# display.net
KiCad netlist of a schematic drawn in EAGLE
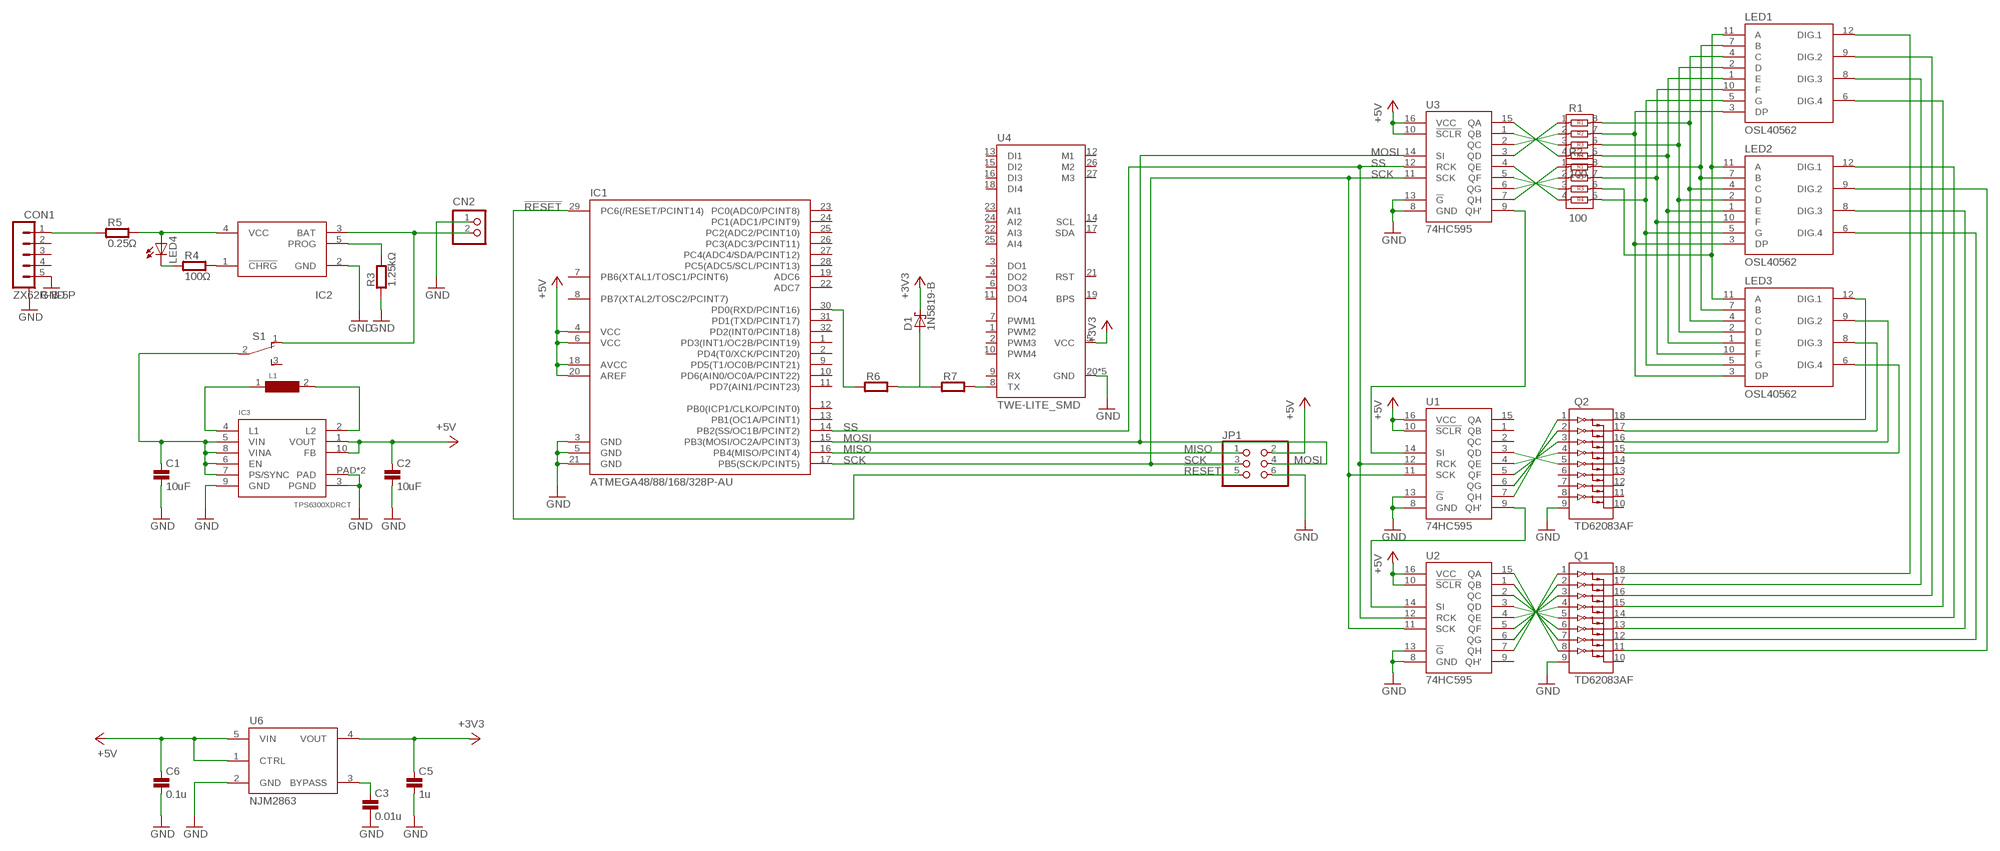
[diagram p0: schematic, sheet 1]

(export (version "E")
  (design (tool "Eeschema 10.0.6"))
  (components
    (comp (ref "C1")
      (value "10uF")
      (footprint "eagle-import:0603@1")
      (libsource (lib "eagle-import") (part "C0603"))
    )
    (comp (ref "C2")
      (value "10uF")
      (footprint "eagle-import:0603@1")
      (libsource (lib "eagle-import") (part "C0603"))
    )
    (comp (ref "C3")
      (value "0.01u")
      (footprint "eagle-import:0603@1")
      (libsource (lib "eagle-import") (part "C0603"))
    )
    (comp (ref "C5")
      (value "1u")
      (footprint "eagle-import:0603@1")
      (libsource (lib "eagle-import") (part "C0603"))
    )
    (comp (ref "C6")
      (value "0.1u")
      (footprint "eagle-import:0603@1")
      (libsource (lib "eagle-import") (part "C0603"))
    )
    (comp (ref "CN2")
      (value "S2B-PH-K-S")
      (footprint "eagle-import:S2B-PH-K-S")
      (libsource (lib "eagle-import") (part "S2B-PH-K-S"))
    )
    (comp (ref "CON1")
      (value "ZX62R-B-5P")
      (footprint "eagle-import:MICRO-B")
      (libsource (lib "eagle-import") (part "ZX62R-B-5P"))
    )
    (comp (ref "D1")
      (value "1N5819-B")
      (footprint "eagle-import:DO41-7.6")
      (libsource (lib "eagle-import") (part "1N5819-B"))
    )
    (comp (ref "IC1")
      (value "ATMEGA48/88/168/328P-AU")
      (footprint "eagle-import:TQFP32")
      (libsource (lib "eagle-import") (part "ATMEGA48/88/168/328P-AU"))
    )
    (comp (ref "IC2")
      (value "LTC4054")
      (footprint "eagle-import:TSOT23-5")
      (libsource (lib "eagle-import") (part "LTC4054"))
    )
    (comp (ref "IC3")
      (value "TPS6300XDRCT")
      (footprint "eagle-import:S-PVSON-N10")
      (libsource (lib "eagle-import") (part "TPS6300XDRCT"))
    )
    (comp (ref "JP1")
      (value "PINHD-2X3")
      (footprint "eagle-import:2X03")
      (libsource (lib "eagle-import") (part "PINHD-2X3"))
    )
    (comp (ref "L1")
      (value "VLF4012ST")
      (footprint "eagle-import:VLF4012ST")
      (libsource (lib "eagle-import") (part "VLF4012ST"))
    )
    (comp (ref "LED1")
      (value "OSL40562")
      (footprint "eagle-import:7SEG_4DIG")
      (libsource (lib "eagle-import") (part "OSL40562"))
    )
    (comp (ref "LED2")
      (value "OSL40562")
      (footprint "eagle-import:7SEG_4DIG")
      (libsource (lib "eagle-import") (part "OSL40562"))
    )
    (comp (ref "LED3")
      (value "OSL40562")
      (footprint "eagle-import:7SEG_4DIG")
      (libsource (lib "eagle-import") (part "OSL40562"))
    )
    (comp (ref "LED4")
      (value "LEDSML0603")
      (footprint "eagle-import:SML0603")
      (libsource (lib "eagle-import") (part "LEDSML0603"))
    )
    (comp (ref "Q1")
      (value "TD62083AF")
      (footprint "eagle-import:SOP18")
      (libsource (lib "eagle-import") (part "TD62083AF"))
    )
    (comp (ref "Q2")
      (value "TD62083AF")
      (footprint "eagle-import:SOP18")
      (libsource (lib "eagle-import") (part "TD62083AF"))
    )
    (comp (ref "R1")
      (value "100")
      (footprint "eagle-import:BCN164AB")
      (libsource (lib "eagle-import") (part "BCN164AB"))
    )
    (comp (ref "R2")
      (value "100")
      (footprint "eagle-import:BCN164AB")
      (libsource (lib "eagle-import") (part "BCN164AB"))
    )
    (comp (ref "R3")
      (value "1.25kΩ")
      (footprint "eagle-import:0603")
      (libsource (lib "eagle-import") (part "R0603"))
    )
    (comp (ref "R4")
      (value "100Ω")
      (footprint "eagle-import:0603")
      (libsource (lib "eagle-import") (part "R0603"))
    )
    (comp (ref "R5")
      (value "0.25Ω")
      (footprint "eagle-import:0603")
      (libsource (lib "eagle-import") (part "R0603"))
    )
    (comp (ref "R6")
      (value "R0204/5")
      (footprint "eagle-import:0204_5")
      (libsource (lib "eagle-import") (part "R0204/5"))
    )
    (comp (ref "R7")
      (value "R0204/5")
      (footprint "eagle-import:0204_5")
      (libsource (lib "eagle-import") (part "R0204/5"))
    )
    (comp (ref "S1")
      (value "SS-12D00")
      (footprint "eagle-import:SS-12D00")
      (libsource (lib "eagle-import") (part "SS-12D00"))
    )
    (comp (ref "U1")
      (value "74HC595")
      (footprint "eagle-import:SOP16")
      (libsource (lib "eagle-import") (part "74HC595"))
    )
    (comp (ref "U2")
      (value "74HC595")
      (footprint "eagle-import:SOP16")
      (libsource (lib "eagle-import") (part "74HC595"))
    )
    (comp (ref "U3")
      (value "74HC595")
      (footprint "eagle-import:SOP16")
      (libsource (lib "eagle-import") (part "74HC595"))
    )
    (comp (ref "U4")
      (value "TWE-LITE_SMD")
      (footprint "eagle-import:LITE")
      (libsource (lib "eagle-import") (part "TWE-LITE_SMD"))
    )
    (comp (ref "U6")
      (value "NJM2863")
      (footprint "eagle-import:SOT23_5PIN")
      (libsource (lib "eagle-import") (part "NJM2863"))
    )
  )
  (nets
    (net (code "1") (name "+3V3") (class "Default")
      (node (ref "C5") (pin "1") (pinfunction "P$1_1") (pintype "passive"))
      (node (ref "D1") (pin "C") (pinfunction "C_C") (pintype "passive"))
      (node (ref "U4") (pin "5") (pinfunction "VCC_5") (pintype "power_in"))
      (node (ref "U6") (pin "4") (pinfunction "VOUT_4") (pintype "output"))
    )
    (net (code "2") (name "+5V") (class "Default")
      (node (ref "C2") (pin "1") (pinfunction "P$1_1") (pintype "passive"))
      (node (ref "C6") (pin "1") (pinfunction "P$1_1") (pintype "passive"))
      (node (ref "IC1") (pin "18") (pinfunction "AVCC_18") (pintype "passive"))
      (node (ref "IC1") (pin "20") (pinfunction "AREF_20") (pintype "passive"))
      (node (ref "IC1") (pin "4") (pinfunction "VCC_4") (pintype "power_in"))
      (node (ref "IC1") (pin "6") (pinfunction "VCC_6") (pintype "power_in"))
      (node (ref "IC3") (pin "1") (pinfunction "VOUT_1") (pintype "output"))
      (node (ref "IC3") (pin "10") (pinfunction "FB_10") (pintype "input"))
      (node (ref "JP1") (pin "2") (pinfunction "2_2") (pintype "passive"))
      (node (ref "U1") (pin "10") (pinfunction "~{SCLR}_10") (pintype "input"))
      (node (ref "U1") (pin "16") (pinfunction "VCC_16") (pintype "power_in"))
      (node (ref "U2") (pin "10") (pinfunction "~{SCLR}_10") (pintype "input"))
      (node (ref "U2") (pin "16") (pinfunction "VCC_16") (pintype "power_in"))
      (node (ref "U3") (pin "10") (pinfunction "~{SCLR}_10") (pintype "input"))
      (node (ref "U3") (pin "16") (pinfunction "VCC_16") (pintype "power_in"))
      (node (ref "U6") (pin "1") (pinfunction "CTRL_1") (pintype "input"))
      (node (ref "U6") (pin "5") (pinfunction "VIN_5") (pintype "input"))
    )
    (net (code "3") (name "/MISO") (class "Default")
      (node (ref "IC1") (pin "16") (pinfunction "PB4(MISO/PCINT4)_16") (pintype "bidirectional"))
      (node (ref "JP1") (pin "1") (pinfunction "1_1") (pintype "passive"))
    )
    (net (code "4") (name "/MOSI") (class "Default")
      (node (ref "IC1") (pin "15") (pinfunction "PB3(MOSI/OC2A/PCINT3)_15") (pintype "bidirectional"))
      (node (ref "JP1") (pin "4") (pinfunction "4_4") (pintype "passive"))
      (node (ref "U3") (pin "14") (pinfunction "SI_14") (pintype "input"))
    )
    (net (code "5") (name "/SCK") (class "Default")
      (node (ref "IC1") (pin "17") (pinfunction "PB5(SCK/PCINT5)_17") (pintype "bidirectional"))
      (node (ref "JP1") (pin "3") (pinfunction "3_3") (pintype "passive"))
      (node (ref "U1") (pin "11") (pinfunction "SCK_11") (pintype "input"))
      (node (ref "U2") (pin "11") (pinfunction "SCK_11") (pintype "input"))
      (node (ref "U3") (pin "11") (pinfunction "SCK_11") (pintype "input"))
    )
    (net (code "6") (name "/SS") (class "Default")
      (node (ref "IC1") (pin "14") (pinfunction "PB2(SS/OC1B/PCINT2)_14") (pintype "bidirectional"))
      (node (ref "U1") (pin "12") (pinfunction "RCK_12") (pintype "input"))
      (node (ref "U2") (pin "12") (pinfunction "RCK_12") (pintype "input"))
      (node (ref "U3") (pin "12") (pinfunction "RCK_12") (pintype "input"))
    )
    (net (code "7") (name "/~{RESET}") (class "Default")
      (node (ref "IC1") (pin "29") (pinfunction "PC6(/RESET/PCINT14)_29") (pintype "bidirectional"))
      (node (ref "JP1") (pin "5") (pinfunction "5_5") (pintype "passive"))
    )
    (net (code "8") (name "GND") (class "Default")
      (node (ref "C1") (pin "2") (pinfunction "P$2_2") (pintype "passive"))
      (node (ref "C2") (pin "2") (pinfunction "P$2_2") (pintype "passive"))
      (node (ref "C3") (pin "2") (pinfunction "P$2_2") (pintype "passive"))
      (node (ref "C5") (pin "2") (pinfunction "P$2_2") (pintype "passive"))
      (node (ref "C6") (pin "2") (pinfunction "P$2_2") (pintype "passive"))
      (node (ref "CN2") (pin "1") (pinfunction "1_1") (pintype "passive"))
      (node (ref "CON1") (pin "5") (pinfunction "5.GND_5") (pintype "passive"))
      (node (ref "CON1") (pin "CASE@1") (pinfunction "P$1_CASE@1") (pintype "bidirectional"))
      (node (ref "CON1") (pin "CASE@2") (pinfunction "P$1_CASE@2") (pintype "bidirectional"))
      (node (ref "CON1") (pin "CASE@3") (pinfunction "P$1_CASE@3") (pintype "bidirectional"))
      (node (ref "CON1") (pin "CASE@4") (pinfunction "P$1_CASE@4") (pintype "bidirectional"))
      (node (ref "IC1") (pin "21") (pinfunction "GND_21") (pintype "power_in"))
      (node (ref "IC1") (pin "3") (pinfunction "GND_3") (pintype "power_in"))
      (node (ref "IC1") (pin "5") (pinfunction "GND_5") (pintype "power_in"))
      (node (ref "IC2") (pin "2") (pinfunction "GND_2") (pintype "power_in"))
      (node (ref "IC3") (pin "3") (pinfunction "PGND_3") (pintype "power_in"))
      (node (ref "IC3") (pin "9") (pinfunction "GND_9") (pintype "power_in"))
      (node (ref "IC3") (pin "PAD") (pinfunction "PAD_PAD") (pintype "power_in"))
      (node (ref "IC3") (pin "PAD@1") (pinfunction "PAD_PAD@1") (pintype "power_in"))
      (node (ref "JP1") (pin "6") (pinfunction "6_6") (pintype "passive"))
      (node (ref "Q1") (pin "9") (pinfunction "GND_9") (pintype "power_in"))
      (node (ref "Q2") (pin "9") (pinfunction "GND_9") (pintype "power_in"))
      (node (ref "R3") (pin "1") (pinfunction "P$1_1") (pintype "passive"))
      (node (ref "U1") (pin "13") (pinfunction "~{G}_13") (pintype "input"))
      (node (ref "U1") (pin "8") (pinfunction "GND_8") (pintype "power_in"))
      (node (ref "U2") (pin "13") (pinfunction "~{G}_13") (pintype "input"))
      (node (ref "U2") (pin "8") (pinfunction "GND_8") (pintype "power_in"))
      (node (ref "U3") (pin "13") (pinfunction "~{G}_13") (pintype "input"))
      (node (ref "U3") (pin "8") (pinfunction "GND_8") (pintype "power_in"))
      (node (ref "U4") (pin "20") (pinfunction "GND_20") (pintype "power_in"))
      (node (ref "U4") (pin "28") (pinfunction "GND_28") (pintype "power_in"))
      (node (ref "U4") (pin "30") (pinfunction "GND_30") (pintype "power_in"))
      (node (ref "U4") (pin "31") (pinfunction "GND_31") (pintype "power_in"))
      (node (ref "U4") (pin "32") (pinfunction "GND_32") (pintype "power_in"))
      (node (ref "U6") (pin "2") (pinfunction "GND_2") (pintype "power_in"))
    )
    (net (code "9") (name "Net-(C1-P$1)") (class "Default")
      (node (ref "C1") (pin "1") (pinfunction "P$1_1") (pintype "passive"))
      (node (ref "IC3") (pin "5") (pinfunction "VIN_5") (pintype "power_in"))
      (node (ref "IC3") (pin "6") (pinfunction "EN_6") (pintype "input"))
      (node (ref "IC3") (pin "7") (pinfunction "PS/SYNC_7") (pintype "input"))
      (node (ref "IC3") (pin "8") (pinfunction "VINA_8") (pintype "power_in"))
      (node (ref "S1") (pin "2") (pinfunction "P_2") (pintype "passive"))
    )
    (net (code "10") (name "Net-(C3-P$1)") (class "Default")
      (node (ref "C3") (pin "1") (pinfunction "P$1_1") (pintype "passive"))
      (node (ref "U6") (pin "3") (pinfunction "BYPASS_3") (pintype "passive"))
    )
    (net (code "11") (name "Net-(CON1-1.VBUS)") (class "Default")
      (node (ref "CON1") (pin "1") (pinfunction "1.VBUS_1") (pintype "passive"))
      (node (ref "R5") (pin "1") (pinfunction "P$1_1") (pintype "passive"))
    )
    (net (code "12") (name "Net-(IC1-PD0(RXD{slash}PCINT16))") (class "Default")
      (node (ref "IC1") (pin "30") (pinfunction "PD0(RXD/PCINT16)_30") (pintype "bidirectional"))
      (node (ref "R6") (pin "1") (pinfunction "P$1_1") (pintype "passive"))
    )
    (net (code "13") (name "Net-(IC2-BAT)") (class "Default")
      (node (ref "CN2") (pin "2") (pinfunction "2_2") (pintype "passive"))
      (node (ref "IC2") (pin "3") (pinfunction "BAT_3") (pintype "power_in"))
      (node (ref "S1") (pin "1") (pinfunction "O_1") (pintype "passive"))
    )
    (net (code "14") (name "Net-(IC2-PROG)") (class "Default")
      (node (ref "IC2") (pin "5") (pinfunction "PROG_5") (pintype "passive"))
      (node (ref "R3") (pin "2") (pinfunction "P$2_2") (pintype "passive"))
    )
    (net (code "15") (name "Net-(IC2-VCC)") (class "Default")
      (node (ref "IC2") (pin "4") (pinfunction "VCC_4") (pintype "power_in"))
      (node (ref "LED4") (pin "A") (pinfunction "A_A") (pintype "passive"))
      (node (ref "R5") (pin "2") (pinfunction "P$2_2") (pintype "passive"))
    )
    (net (code "16") (name "Net-(IC2-~{CHRG})") (class "Default")
      (node (ref "IC2") (pin "1") (pinfunction "~{CHRG}_1") (pintype "output"))
      (node (ref "R4") (pin "2") (pinfunction "P$2_2") (pintype "passive"))
    )
    (net (code "17") (name "Net-(IC3-L1)") (class "Default")
      (node (ref "IC3") (pin "4") (pinfunction "L1_4") (pintype "bidirectional"))
      (node (ref "L1") (pin "1") (pinfunction "1_1") (pintype "passive"))
    )
    (net (code "18") (name "Net-(IC3-L2)") (class "Default")
      (node (ref "IC3") (pin "2") (pinfunction "L2_2") (pintype "bidirectional"))
      (node (ref "L1") (pin "2") (pinfunction "2_2") (pintype "passive"))
    )
    (net (code "19") (name "Net-(LED1-A)") (class "Default")
      (node (ref "LED1") (pin "11") (pinfunction "A_11") (pintype "input"))
      (node (ref "LED2") (pin "11") (pinfunction "A_11") (pintype "input"))
      (node (ref "LED3") (pin "11") (pinfunction "A_11") (pintype "input"))
      (node (ref "R2") (pin "6") (pinfunction "6_6") (pintype "passive"))
    )
    (net (code "20") (name "Net-(LED1-B)") (class "Default")
      (node (ref "LED1") (pin "7") (pinfunction "B_7") (pintype "input"))
      (node (ref "LED2") (pin "7") (pinfunction "B_7") (pintype "input"))
      (node (ref "LED3") (pin "7") (pinfunction "B_7") (pintype "input"))
      (node (ref "R2") (pin "8") (pinfunction "8_8") (pintype "passive"))
    )
    (net (code "21") (name "Net-(LED1-C)") (class "Default")
      (node (ref "LED1") (pin "4") (pinfunction "C_4") (pintype "input"))
      (node (ref "LED2") (pin "4") (pinfunction "C_4") (pintype "input"))
      (node (ref "LED3") (pin "4") (pinfunction "C_4") (pintype "input"))
      (node (ref "R1") (pin "8") (pinfunction "8_8") (pintype "passive"))
    )
    (net (code "22") (name "Net-(LED1-D)") (class "Default")
      (node (ref "LED1") (pin "2") (pinfunction "D_2") (pintype "input"))
      (node (ref "LED2") (pin "2") (pinfunction "D_2") (pintype "input"))
      (node (ref "LED3") (pin "2") (pinfunction "D_2") (pintype "input"))
      (node (ref "R1") (pin "6") (pinfunction "6_6") (pintype "passive"))
    )
    (net (code "23") (name "Net-(LED1-DIG.1)") (class "Default")
      (node (ref "LED1") (pin "12") (pinfunction "DIG.1_12") (pintype "output"))
      (node (ref "Q1") (pin "18") (pinfunction "O1_18") (pintype "output"))
    )
    (net (code "24") (name "Net-(LED1-DIG.2)") (class "Default")
      (node (ref "LED1") (pin "9") (pinfunction "DIG.2_9") (pintype "output"))
      (node (ref "Q1") (pin "16") (pinfunction "O3_16") (pintype "output"))
    )
    (net (code "25") (name "Net-(LED1-DIG.3)") (class "Default")
      (node (ref "LED1") (pin "8") (pinfunction "DIG.3_8") (pintype "output"))
      (node (ref "Q1") (pin "17") (pinfunction "O2_17") (pintype "output"))
    )
    (net (code "26") (name "Net-(LED1-DIG.4)") (class "Default")
      (node (ref "LED1") (pin "6") (pinfunction "DIG.4_6") (pintype "output"))
      (node (ref "Q1") (pin "15") (pinfunction "O4_15") (pintype "output"))
    )
    (net (code "27") (name "Net-(LED1-DP)") (class "Default")
      (node (ref "LED1") (pin "3") (pinfunction "DP_3") (pintype "input"))
      (node (ref "LED2") (pin "3") (pinfunction "DP_3") (pintype "input"))
      (node (ref "LED3") (pin "3") (pinfunction "DP_3") (pintype "input"))
      (node (ref "R1") (pin "7") (pinfunction "7_7") (pintype "passive"))
    )
    (net (code "28") (name "Net-(LED1-E)") (class "Default")
      (node (ref "LED1") (pin "1") (pinfunction "E_1") (pintype "input"))
      (node (ref "LED2") (pin "1") (pinfunction "E_1") (pintype "input"))
      (node (ref "LED3") (pin "1") (pinfunction "E_1") (pintype "input"))
      (node (ref "R1") (pin "5") (pinfunction "5_5") (pintype "passive"))
    )
    (net (code "29") (name "Net-(LED1-F)") (class "Default")
      (node (ref "LED1") (pin "10") (pinfunction "F_10") (pintype "input"))
      (node (ref "LED2") (pin "10") (pinfunction "F_10") (pintype "input"))
      (node (ref "LED3") (pin "10") (pinfunction "F_10") (pintype "input"))
      (node (ref "R2") (pin "7") (pinfunction "7_7") (pintype "passive"))
    )
    (net (code "30") (name "Net-(LED1-G)") (class "Default")
      (node (ref "LED1") (pin "5") (pinfunction "G_5") (pintype "input"))
      (node (ref "LED2") (pin "5") (pinfunction "G_5") (pintype "input"))
      (node (ref "LED3") (pin "5") (pinfunction "G_5") (pintype "input"))
      (node (ref "R2") (pin "5") (pinfunction "5_5") (pintype "passive"))
    )
    (net (code "31") (name "Net-(LED2-DIG.1)") (class "Default")
      (node (ref "LED2") (pin "12") (pinfunction "DIG.1_12") (pintype "output"))
      (node (ref "Q1") (pin "14") (pinfunction "O5_14") (pintype "output"))
    )
    (net (code "32") (name "Net-(LED2-DIG.2)") (class "Default")
      (node (ref "LED2") (pin "9") (pinfunction "DIG.2_9") (pintype "output"))
      (node (ref "Q1") (pin "11") (pinfunction "O8_11") (pintype "output"))
    )
    (net (code "33") (name "Net-(LED2-DIG.3)") (class "Default")
      (node (ref "LED2") (pin "8") (pinfunction "DIG.3_8") (pintype "output"))
      (node (ref "Q1") (pin "13") (pinfunction "O6_13") (pintype "output"))
    )
    (net (code "34") (name "Net-(LED2-DIG.4)") (class "Default")
      (node (ref "LED2") (pin "6") (pinfunction "DIG.4_6") (pintype "output"))
      (node (ref "Q1") (pin "12") (pinfunction "O7_12") (pintype "output"))
    )
    (net (code "35") (name "Net-(LED3-DIG.1)") (class "Default")
      (node (ref "LED3") (pin "12") (pinfunction "DIG.1_12") (pintype "output"))
      (node (ref "Q2") (pin "18") (pinfunction "O1_18") (pintype "output"))
    )
    (net (code "36") (name "Net-(LED3-DIG.2)") (class "Default")
      (node (ref "LED3") (pin "9") (pinfunction "DIG.2_9") (pintype "output"))
      (node (ref "Q2") (pin "16") (pinfunction "O3_16") (pintype "output"))
    )
    (net (code "37") (name "Net-(LED3-DIG.3)") (class "Default")
      (node (ref "LED3") (pin "8") (pinfunction "DIG.3_8") (pintype "output"))
      (node (ref "Q2") (pin "17") (pinfunction "O2_17") (pintype "output"))
    )
    (net (code "38") (name "Net-(LED3-DIG.4)") (class "Default")
      (node (ref "LED3") (pin "6") (pinfunction "DIG.4_6") (pintype "output"))
      (node (ref "Q2") (pin "15") (pinfunction "O4_15") (pintype "output"))
    )
    (net (code "39") (name "Net-(Q1-I1)") (class "Default")
      (node (ref "Q1") (pin "1") (pinfunction "I1_1") (pintype "input"))
      (node (ref "U2") (pin "7") (pinfunction "QH_7") (pintype "output"))
    )
    (net (code "40") (name "Net-(Q1-I2)") (class "Default")
      (node (ref "Q1") (pin "2") (pinfunction "I2_2") (pintype "input"))
      (node (ref "U2") (pin "6") (pinfunction "QG_6") (pintype "output"))
    )
    (net (code "41") (name "Net-(Q1-I3)") (class "Default")
      (node (ref "Q1") (pin "3") (pinfunction "I3_3") (pintype "input"))
      (node (ref "U2") (pin "5") (pinfunction "QF_5") (pintype "output"))
    )
    (net (code "42") (name "Net-(Q1-I4)") (class "Default")
      (node (ref "Q1") (pin "4") (pinfunction "I4_4") (pintype "input"))
      (node (ref "U2") (pin "4") (pinfunction "QE_4") (pintype "output"))
    )
    (net (code "43") (name "Net-(Q1-I5)") (class "Default")
      (node (ref "Q1") (pin "5") (pinfunction "I5_5") (pintype "input"))
      (node (ref "U2") (pin "3") (pinfunction "QD_3") (pintype "output"))
    )
    (net (code "44") (name "Net-(Q1-I6)") (class "Default")
      (node (ref "Q1") (pin "6") (pinfunction "I6_6") (pintype "input"))
      (node (ref "U2") (pin "2") (pinfunction "QC_2") (pintype "output"))
    )
    (net (code "45") (name "Net-(Q1-I7)") (class "Default")
      (node (ref "Q1") (pin "7") (pinfunction "I7_7") (pintype "input"))
      (node (ref "U2") (pin "1") (pinfunction "QB_1") (pintype "output"))
    )
    (net (code "46") (name "Net-(Q1-I8)") (class "Default")
      (node (ref "Q1") (pin "8") (pinfunction "I8_8") (pintype "input"))
      (node (ref "U2") (pin "15") (pinfunction "QA_15") (pintype "output"))
    )
    (net (code "47") (name "Net-(Q2-I1)") (class "Default")
      (node (ref "Q2") (pin "1") (pinfunction "I1_1") (pintype "input"))
      (node (ref "U1") (pin "7") (pinfunction "QH_7") (pintype "output"))
    )
    (net (code "48") (name "Net-(Q2-I2)") (class "Default")
      (node (ref "Q2") (pin "2") (pinfunction "I2_2") (pintype "input"))
      (node (ref "U1") (pin "6") (pinfunction "QG_6") (pintype "output"))
    )
    (net (code "49") (name "Net-(Q2-I3)") (class "Default")
      (node (ref "Q2") (pin "3") (pinfunction "I3_3") (pintype "input"))
      (node (ref "U1") (pin "5") (pinfunction "QF_5") (pintype "output"))
    )
    (net (code "50") (name "Net-(Q2-I4)") (class "Default")
      (node (ref "Q2") (pin "4") (pinfunction "I4_4") (pintype "input"))
      (node (ref "U1") (pin "4") (pinfunction "QE_4") (pintype "output"))
    )
    (net (code "51") (name "Net-(Q2-I5)") (class "Default")
      (node (ref "Q2") (pin "5") (pinfunction "I5_5") (pintype "input"))
      (node (ref "U1") (pin "3") (pinfunction "QD_3") (pintype "output"))
    )
    (net (code "52") (name "Net-(R4-P$1)") (class "Default")
      (node (ref "LED4") (pin "C") (pinfunction "C_C") (pintype "passive"))
      (node (ref "R4") (pin "1") (pinfunction "P$1_1") (pintype "passive"))
    )
    (net (code "53") (name "Net-(R6-P$2)") (class "Default")
      (node (ref "D1") (pin "A") (pinfunction "A_A") (pintype "passive"))
      (node (ref "R6") (pin "2") (pinfunction "P$2_2") (pintype "passive"))
      (node (ref "R7") (pin "1") (pinfunction "P$1_1") (pintype "passive"))
    )
    (net (code "54") (name "Net-(R7-P$2)") (class "Default")
      (node (ref "R7") (pin "2") (pinfunction "P$2_2") (pintype "passive"))
      (node (ref "U4") (pin "8") (pinfunction "TX_8") (pintype "output"))
    )
    (net (code "55") (name "Net-(U1-QH')") (class "Default")
      (node (ref "U1") (pin "9") (pinfunction "QH'_9") (pintype "output"))
      (node (ref "U2") (pin "14") (pinfunction "SI_14") (pintype "input"))
    )
    (net (code "56") (name "Net-(U1-SI)") (class "Default")
      (node (ref "U1") (pin "14") (pinfunction "SI_14") (pintype "input"))
      (node (ref "U3") (pin "9") (pinfunction "QH'_9") (pintype "output"))
    )
    (net (code "57") (name "Net-(U3-QA)") (class "Default")
      (node (ref "R1") (pin "4") (pinfunction "4_4") (pintype "passive"))
      (node (ref "U3") (pin "15") (pinfunction "QA_15") (pintype "output"))
    )
    (net (code "58") (name "Net-(U3-QB)") (class "Default")
      (node (ref "R1") (pin "3") (pinfunction "3_3") (pintype "passive"))
      (node (ref "U3") (pin "1") (pinfunction "QB_1") (pintype "output"))
    )
    (net (code "59") (name "Net-(U3-QC)") (class "Default")
      (node (ref "R1") (pin "2") (pinfunction "2_2") (pintype "passive"))
      (node (ref "U3") (pin "2") (pinfunction "QC_2") (pintype "output"))
    )
    (net (code "60") (name "Net-(U3-QD)") (class "Default")
      (node (ref "R1") (pin "1") (pinfunction "1_1") (pintype "passive"))
      (node (ref "U3") (pin "3") (pinfunction "QD_3") (pintype "output"))
    )
    (net (code "61") (name "Net-(U3-QE)") (class "Default")
      (node (ref "R2") (pin "4") (pinfunction "4_4") (pintype "passive"))
      (node (ref "U3") (pin "4") (pinfunction "QE_4") (pintype "output"))
    )
    (net (code "62") (name "Net-(U3-QF)") (class "Default")
      (node (ref "R2") (pin "3") (pinfunction "3_3") (pintype "passive"))
      (node (ref "U3") (pin "5") (pinfunction "QF_5") (pintype "output"))
    )
    (net (code "63") (name "Net-(U3-QG)") (class "Default")
      (node (ref "R2") (pin "2") (pinfunction "2_2") (pintype "passive"))
      (node (ref "U3") (pin "6") (pinfunction "QG_6") (pintype "output"))
    )
    (net (code "64") (name "Net-(U3-QH)") (class "Default")
      (node (ref "R2") (pin "1") (pinfunction "1_1") (pintype "passive"))
      (node (ref "U3") (pin "7") (pinfunction "QH_7") (pintype "output"))
    )
    (net (code "65") (name "unconnected-(CON1-2.D--Pad2)") (class "Default")
      (node (ref "CON1") (pin "2") (pinfunction "2.D-_2") (pintype "passive"))
    )
    (net (code "66") (name "unconnected-(CON1-3.D+-Pad3)") (class "Default")
      (node (ref "CON1") (pin "3") (pinfunction "3.D+_3") (pintype "passive"))
    )
    (net (code "67") (name "unconnected-(CON1-4.ID-Pad4)") (class "Default")
      (node (ref "CON1") (pin "4") (pinfunction "4.ID_4") (pintype "passive"))
    )
    (net (code "68") (name "unconnected-(IC1-ADC6-Pad19)") (class "Default")
      (node (ref "IC1") (pin "19") (pinfunction "ADC6_19") (pintype "passive"))
    )
    (net (code "69") (name "unconnected-(IC1-ADC7-Pad22)") (class "Default")
      (node (ref "IC1") (pin "22") (pinfunction "ADC7_22") (pintype "passive"))
    )
    (net (code "70") (name "unconnected-(IC1-PB0(ICP1{slash}CLKO{slash}PCINT0)-Pad12)") (class "Default")
      (node (ref "IC1") (pin "12") (pinfunction "PB0(ICP1/CLKO/PCINT0)_12") (pintype "bidirectional"))
    )
    (net (code "71") (name "unconnected-(IC1-PB1(OC1A{slash}PCINT1)-Pad13)") (class "Default")
      (node (ref "IC1") (pin "13") (pinfunction "PB1(OC1A/PCINT1)_13") (pintype "bidirectional"))
    )
    (net (code "72") (name "unconnected-(IC1-PB6(XTAL1{slash}TOSC1{slash}PCINT6)-Pad7)") (class "Default")
      (node (ref "IC1") (pin "7") (pinfunction "PB6(XTAL1/TOSC1/PCINT6)_7") (pintype "bidirectional"))
    )
    (net (code "73") (name "unconnected-(IC1-PB7(XTAL2{slash}TOSC2{slash}PCINT7)-Pad8)") (class "Default")
      (node (ref "IC1") (pin "8") (pinfunction "PB7(XTAL2/TOSC2/PCINT7)_8") (pintype "bidirectional"))
    )
    (net (code "74") (name "unconnected-(IC1-PC0(ADC0{slash}PCINT8)-Pad23)") (class "Default")
      (node (ref "IC1") (pin "23") (pinfunction "PC0(ADC0/PCINT8)_23") (pintype "bidirectional"))
    )
    (net (code "75") (name "unconnected-(IC1-PC1(ADC1{slash}PCINT9)-Pad24)") (class "Default")
      (node (ref "IC1") (pin "24") (pinfunction "PC1(ADC1/PCINT9)_24") (pintype "bidirectional"))
    )
    (net (code "76") (name "unconnected-(IC1-PC2(ADC2{slash}PCINT10)-Pad25)") (class "Default")
      (node (ref "IC1") (pin "25") (pinfunction "PC2(ADC2/PCINT10)_25") (pintype "bidirectional"))
    )
    (net (code "77") (name "unconnected-(IC1-PC3(ADC3{slash}PCINT11)-Pad26)") (class "Default")
      (node (ref "IC1") (pin "26") (pinfunction "PC3(ADC3/PCINT11)_26") (pintype "bidirectional"))
    )
    (net (code "78") (name "unconnected-(IC1-PC4(ADC4{slash}SDA{slash}PCINT12)-Pad27)") (class "Default")
      (node (ref "IC1") (pin "27") (pinfunction "PC4(ADC4/SDA/PCINT12)_27") (pintype "bidirectional"))
    )
    (net (code "79") (name "unconnected-(IC1-PC5(ADC5{slash}SCL{slash}PCINT13)-Pad28)") (class "Default")
      (node (ref "IC1") (pin "28") (pinfunction "PC5(ADC5/SCL/PCINT13)_28") (pintype "bidirectional"))
    )
    (net (code "80") (name "unconnected-(IC1-PD1(TXD{slash}PCINT17)-Pad31)") (class "Default")
      (node (ref "IC1") (pin "31") (pinfunction "PD1(TXD/PCINT17)_31") (pintype "bidirectional"))
    )
    (net (code "81") (name "unconnected-(IC1-PD2(INT0{slash}PCINT18)-Pad32)") (class "Default")
      (node (ref "IC1") (pin "32") (pinfunction "PD2(INT0/PCINT18)_32") (pintype "bidirectional"))
    )
    (net (code "82") (name "unconnected-(IC1-PD3(INT1{slash}OC2B{slash}PCINT19)-Pad1)") (class "Default")
      (node (ref "IC1") (pin "1") (pinfunction "PD3(INT1/OC2B/PCINT19)_1") (pintype "bidirectional"))
    )
    (net (code "83") (name "unconnected-(IC1-PD4(T0{slash}XCK{slash}PCINT20)-Pad2)") (class "Default")
      (node (ref "IC1") (pin "2") (pinfunction "PD4(T0/XCK/PCINT20)_2") (pintype "bidirectional"))
    )
    (net (code "84") (name "unconnected-(IC1-PD5(T1{slash}OC0B{slash}PCINT21)-Pad9)") (class "Default")
      (node (ref "IC1") (pin "9") (pinfunction "PD5(T1/OC0B/PCINT21)_9") (pintype "bidirectional"))
    )
    (net (code "85") (name "unconnected-(IC1-PD6(AIN0{slash}OC0A{slash}PCINT22)-Pad10)") (class "Default")
      (node (ref "IC1") (pin "10") (pinfunction "PD6(AIN0/OC0A/PCINT22)_10") (pintype "bidirectional"))
    )
    (net (code "86") (name "unconnected-(IC1-PD7(AIN1{slash}PCINT23)-Pad11)") (class "Default")
      (node (ref "IC1") (pin "11") (pinfunction "PD7(AIN1/PCINT23)_11") (pintype "bidirectional"))
    )
    (net (code "87") (name "unconnected-(Q1-COMMON-Pad10)") (class "Default")
      (node (ref "Q1") (pin "10") (pinfunction "COMMON_10") (pintype "output"))
    )
    (net (code "88") (name "unconnected-(Q2-COMMON-Pad10)") (class "Default")
      (node (ref "Q2") (pin "10") (pinfunction "COMMON_10") (pintype "output"))
    )
    (net (code "89") (name "unconnected-(Q2-I6-Pad6)") (class "Default")
      (node (ref "Q2") (pin "6") (pinfunction "I6_6") (pintype "input"))
    )
    (net (code "90") (name "unconnected-(Q2-I7-Pad7)") (class "Default")
      (node (ref "Q2") (pin "7") (pinfunction "I7_7") (pintype "input"))
    )
    (net (code "91") (name "unconnected-(Q2-I8-Pad8)") (class "Default")
      (node (ref "Q2") (pin "8") (pinfunction "I8_8") (pintype "input"))
    )
    (net (code "92") (name "unconnected-(Q2-O5-Pad14)") (class "Default")
      (node (ref "Q2") (pin "14") (pinfunction "O5_14") (pintype "output"))
    )
    (net (code "93") (name "unconnected-(Q2-O6-Pad13)") (class "Default")
      (node (ref "Q2") (pin "13") (pinfunction "O6_13") (pintype "output"))
    )
    (net (code "94") (name "unconnected-(Q2-O7-Pad12)") (class "Default")
      (node (ref "Q2") (pin "12") (pinfunction "O7_12") (pintype "output"))
    )
    (net (code "95") (name "unconnected-(Q2-O8-Pad11)") (class "Default")
      (node (ref "Q2") (pin "11") (pinfunction "O8_11") (pintype "output"))
    )
    (net (code "96") (name "unconnected-(S1-S-Pad3)") (class "Default")
      (node (ref "S1") (pin "3") (pinfunction "S_3") (pintype "passive"))
    )
    (net (code "97") (name "unconnected-(U1-QA-Pad15)") (class "Default")
      (node (ref "U1") (pin "15") (pinfunction "QA_15") (pintype "output"))
    )
    (net (code "98") (name "unconnected-(U1-QB-Pad1)") (class "Default")
      (node (ref "U1") (pin "1") (pinfunction "QB_1") (pintype "output"))
    )
    (net (code "99") (name "unconnected-(U1-QC-Pad2)") (class "Default")
      (node (ref "U1") (pin "2") (pinfunction "QC_2") (pintype "output"))
    )
    (net (code "100") (name "unconnected-(U2-QH'-Pad9)") (class "Default")
      (node (ref "U2") (pin "9") (pinfunction "QH'_9") (pintype "output"))
    )
    (net (code "101") (name "unconnected-(U4-AI1-Pad23)") (class "Default")
      (node (ref "U4") (pin "23") (pinfunction "AI1_23") (pintype "input"))
    )
    (net (code "102") (name "unconnected-(U4-AI2-Pad24)") (class "Default")
      (node (ref "U4") (pin "24") (pinfunction "AI2_24") (pintype "input"))
    )
    (net (code "103") (name "unconnected-(U4-AI3-Pad22)") (class "Default")
      (node (ref "U4") (pin "22") (pinfunction "AI3_22") (pintype "input"))
    )
    (net (code "104") (name "unconnected-(U4-AI4-Pad25)") (class "Default")
      (node (ref "U4") (pin "25") (pinfunction "AI4_25") (pintype "input"))
    )
    (net (code "105") (name "unconnected-(U4-BPS-Pad19)") (class "Default")
      (node (ref "U4") (pin "19") (pinfunction "BPS_19") (pintype "input"))
    )
    (net (code "106") (name "unconnected-(U4-DI1-Pad13)") (class "Default")
      (node (ref "U4") (pin "13") (pinfunction "DI1_13") (pintype "input"))
    )
    (net (code "107") (name "unconnected-(U4-DI2-Pad15)") (class "Default")
      (node (ref "U4") (pin "15") (pinfunction "DI2_15") (pintype "input"))
    )
    (net (code "108") (name "unconnected-(U4-DI3-Pad16)") (class "Default")
      (node (ref "U4") (pin "16") (pinfunction "DI3_16") (pintype "input"))
    )
    (net (code "109") (name "unconnected-(U4-DI4-Pad18)") (class "Default")
      (node (ref "U4") (pin "18") (pinfunction "DI4_18") (pintype "input"))
    )
    (net (code "110") (name "unconnected-(U4-DO1-Pad3)") (class "Default")
      (node (ref "U4") (pin "3") (pinfunction "DO1_3") (pintype "output"))
    )
    (net (code "111") (name "unconnected-(U4-DO2-Pad4)") (class "Default")
      (node (ref "U4") (pin "4") (pinfunction "DO2_4") (pintype "output"))
    )
    (net (code "112") (name "unconnected-(U4-DO3-Pad6)") (class "Default")
      (node (ref "U4") (pin "6") (pinfunction "DO3_6") (pintype "output"))
    )
    (net (code "113") (name "unconnected-(U4-DO4-Pad11)") (class "Default")
      (node (ref "U4") (pin "11") (pinfunction "DO4_11") (pintype "output"))
    )
    (net (code "114") (name "unconnected-(U4-M1-Pad12)") (class "Default")
      (node (ref "U4") (pin "12") (pinfunction "M1_12") (pintype "input"))
    )
    (net (code "115") (name "unconnected-(U4-M2-Pad26)") (class "Default")
      (node (ref "U4") (pin "26") (pinfunction "M2_26") (pintype "input"))
    )
    (net (code "116") (name "unconnected-(U4-M3-Pad27)") (class "Default")
      (node (ref "U4") (pin "27") (pinfunction "M3_27") (pintype "input"))
    )
    (net (code "117") (name "unconnected-(U4-PWM1-Pad7)") (class "Default")
      (node (ref "U4") (pin "7") (pinfunction "PWM1_7") (pintype "output"))
    )
    (net (code "118") (name "unconnected-(U4-PWM2-Pad1)") (class "Default")
      (node (ref "U4") (pin "1") (pinfunction "PWM2_1") (pintype "output"))
    )
    (net (code "119") (name "unconnected-(U4-PWM3-Pad2)") (class "Default")
      (node (ref "U4") (pin "2") (pinfunction "PWM3_2") (pintype "output"))
    )
    (net (code "120") (name "unconnected-(U4-PWM4-Pad10)") (class "Default")
      (node (ref "U4") (pin "10") (pinfunction "PWM4_10") (pintype "output"))
    )
    (net (code "121") (name "unconnected-(U4-RST-Pad21)") (class "Default")
      (node (ref "U4") (pin "21") (pinfunction "RST_21") (pintype "input"))
    )
    (net (code "122") (name "unconnected-(U4-RX-Pad9)") (class "Default")
      (node (ref "U4") (pin "9") (pinfunction "RX_9") (pintype "input"))
    )
    (net (code "123") (name "unconnected-(U4-SCL-Pad14)") (class "Default")
      (node (ref "U4") (pin "14") (pinfunction "SCL_14") (pintype "bidirectional"))
    )
    (net (code "124") (name "unconnected-(U4-SDA-Pad17)") (class "Default")
      (node (ref "U4") (pin "17") (pinfunction "SDA_17") (pintype "bidirectional"))
    )
  )
)
